# cam_cross_link.net
KiCad netlist of a schematic drawn in Altium Designer
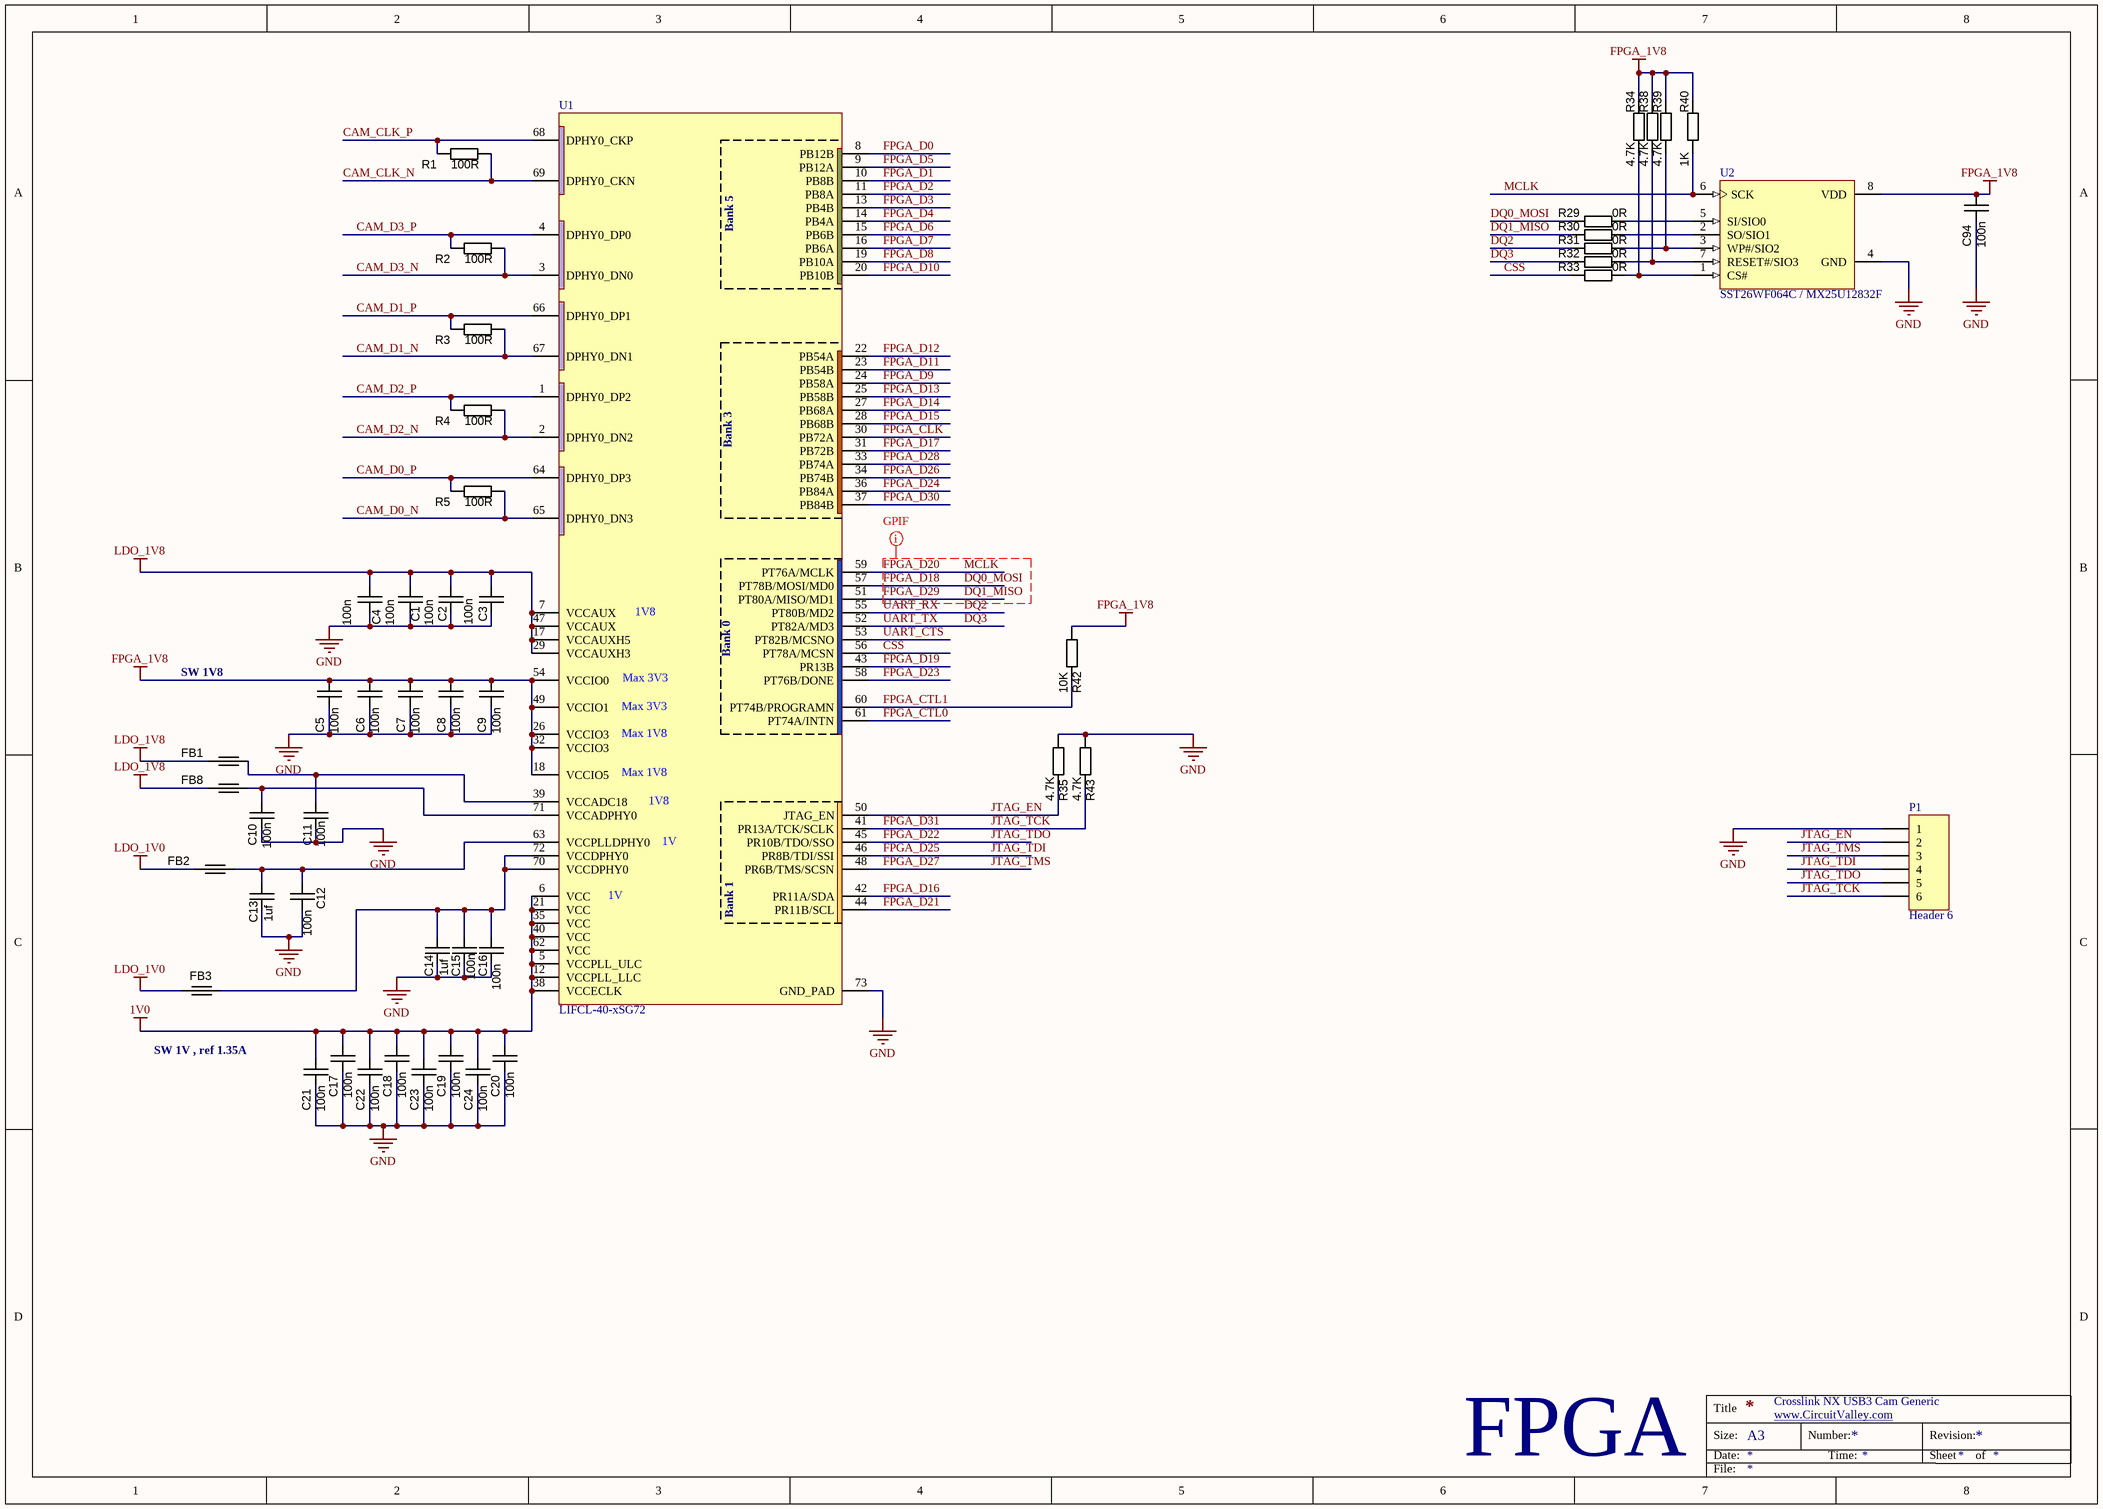
[diagram p0: cam_cross_link.SchDoc]

(export (version "E")
  (design (tool "Eeschema 10.0.6"))
  (components
    (comp (ref "C1")
      (value "100n")
      (footprint "CAPC1608N")
      (description "Capacitor SMD Cer 10pF 5% 50V NP0 0603")
      (fields (field (name "TOLERANCE") "±5%") (field (name "PART") "C0603X104K5RAC"))
      (libsource (lib "PBL - Capacitors") (part "CAPC_10p_0603_NP0_1%_50V"))
    )
    (comp (ref "C2")
      (value "100n")
      (footprint "CAPC1608N")
      (description "Capacitor SMD Cer 10pF 5% 50V NP0 0603")
      (fields (field (name "TOLERANCE") "±5%") (field (name "PART") "C0603X104K5RAC"))
      (libsource (lib "PBL - Capacitors") (part "CAPC_10p_0603_NP0_1%_50V"))
    )
    (comp (ref "C3")
      (value "100n")
      (footprint "CAPC1608N")
      (description "Capacitor SMD Cer 10pF 5% 50V NP0 0603")
      (fields (field (name "TOLERANCE") "±5%") (field (name "PART") "C0603X104K5RAC"))
      (libsource (lib "PBL - Capacitors") (part "CAPC_10p_0603_NP0_1%_50V"))
    )
    (comp (ref "C4")
      (value "100n")
      (footprint "CAPC1608N")
      (description "Capacitor SMD Cer 10pF 5% 50V NP0 0603")
      (fields (field (name "TOLERANCE") "±5%") (field (name "PART") "C0603X104K5RAC"))
      (libsource (lib "PBL - Capacitors") (part "CAPC_10p_0603_NP0_1%_50V"))
    )
    (comp (ref "C5")
      (value "100n")
      (footprint "CAPC1608N")
      (description "Capacitor SMD Cer 10pF 5% 50V NP0 0603")
      (fields (field (name "TOLERANCE") "±5%") (field (name "PART") "C0603X104K5RAC"))
      (libsource (lib "PBL - Capacitors") (part "CAPC_10p_0603_NP0_1%_50V"))
    )
    (comp (ref "C6")
      (value "100n")
      (footprint "CAPC1608N")
      (description "Capacitor SMD Cer 10pF 5% 50V NP0 0603")
      (fields (field (name "TOLERANCE") "±5%") (field (name "PART") "C0603X104K5RAC"))
      (libsource (lib "PBL - Capacitors") (part "CAPC_10p_0603_NP0_1%_50V"))
    )
    (comp (ref "C7")
      (value "100n")
      (footprint "CAPC1608N")
      (description "Capacitor SMD Cer 10pF 5% 50V NP0 0603")
      (fields (field (name "TOLERANCE") "±5%") (field (name "PART") "C0603X104K5RAC"))
      (libsource (lib "PBL - Capacitors") (part "CAPC_10p_0603_NP0_1%_50V"))
    )
    (comp (ref "C8")
      (value "100n")
      (footprint "CAPC1608N")
      (description "Capacitor SMD Cer 10pF 5% 50V NP0 0603")
      (fields (field (name "TOLERANCE") "±5%") (field (name "PART") "C0603X104K5RAC"))
      (libsource (lib "PBL - Capacitors") (part "CAPC_10p_0603_NP0_1%_50V"))
    )
    (comp (ref "C9")
      (value "100n")
      (footprint "CAPC1608N")
      (description "Capacitor SMD Cer 10pF 5% 50V NP0 0603")
      (fields (field (name "TOLERANCE") "±5%") (field (name "PART") "C0603X104K5RAC"))
      (libsource (lib "PBL - Capacitors") (part "CAPC_10p_0603_NP0_1%_50V"))
    )
    (comp (ref "C10")
      (value "100n")
      (footprint "CAPC1608N")
      (description "Capacitor SMD Cer 10pF 5% 50V NP0 0603")
      (fields (field (name "TOLERANCE") "±5%") (field (name "PART") "C0603X104K5RAC"))
      (libsource (lib "PBL - Capacitors") (part "CAPC_10p_0603_NP0_1%_50V"))
    )
    (comp (ref "C11")
      (value "100n")
      (footprint "CAPC1608N")
      (description "Capacitor SMD Cer 10pF 5% 50V NP0 0603")
      (fields (field (name "TOLERANCE") "±5%") (field (name "PART") "C0603X104K5RAC"))
      (libsource (lib "PBL - Capacitors") (part "CAPC_10p_0603_NP0_1%_50V"))
    )
    (comp (ref "C12")
      (value "100n")
      (footprint "CAPC1608N")
      (description "Capacitor SMD Cer 10pF 5% 50V NP0 0603")
      (fields (field (name "TOLERANCE") "±5%") (field (name "PART") "C0603X104K5RAC"))
      (libsource (lib "PBL - Capacitors") (part "CAPC_10p_0603_NP0_1%_50V"))
    )
    (comp (ref "C13")
      (value "1uf")
      (footprint "CAPC1608N")
      (description "Capacitor SMD Cer 10pF 5% 50V NP0 0603")
      (fields (field (name "TOLERANCE") "±5%") (field (name "PART") "C0603X104K5RAC"))
      (libsource (lib "PBL - Capacitors") (part "CAPC_10p_0603_NP0_1%_50V"))
    )
    (comp (ref "C14")
      (value "1uf")
      (footprint "CAPC1608N")
      (description "Capacitor SMD Cer 10pF 5% 50V NP0 0603")
      (fields (field (name "TOLERANCE") "±5%") (field (name "PART") "C0603X104K5RAC"))
      (libsource (lib "PBL - Capacitors") (part "CAPC_10p_0603_NP0_1%_50V"))
    )
    (comp (ref "C15")
      (value "100n")
      (footprint "CAPC1608N")
      (description "Capacitor SMD Cer 10pF 5% 50V NP0 0603")
      (fields (field (name "TOLERANCE") "±5%") (field (name "PART") "C0603X104K5RAC"))
      (libsource (lib "PBL - Capacitors") (part "CAPC_10p_0603_NP0_1%_50V"))
    )
    (comp (ref "C16")
      (value "100n")
      (footprint "CAPC1608N")
      (description "Capacitor SMD Cer 10pF 5% 50V NP0 0603")
      (fields (field (name "TOLERANCE") "±5%") (field (name "PART") "C0603X104K5RAC"))
      (libsource (lib "PBL - Capacitors") (part "CAPC_10p_0603_NP0_1%_50V"))
    )
    (comp (ref "C17")
      (value "100n")
      (footprint "CAPC1608N")
      (description "Capacitor SMD Cer 10pF 5% 50V NP0 0603")
      (fields (field (name "TOLERANCE") "±5%") (field (name "PART") "C0603X104K5RAC"))
      (libsource (lib "PBL - Capacitors") (part "CAPC_10p_0603_NP0_1%_50V"))
    )
    (comp (ref "C18")
      (value "100n")
      (footprint "CAPC1608N")
      (description "Capacitor SMD Cer 10pF 5% 50V NP0 0603")
      (fields (field (name "TOLERANCE") "±5%") (field (name "PART") "C0603X104K5RAC"))
      (libsource (lib "PBL - Capacitors") (part "CAPC_10p_0603_NP0_1%_50V"))
    )
    (comp (ref "C19")
      (value "100n")
      (footprint "CAPC1608N")
      (description "Capacitor SMD Cer 10pF 5% 50V NP0 0603")
      (fields (field (name "TOLERANCE") "±5%") (field (name "PART") "C0603X104K5RAC"))
      (libsource (lib "PBL - Capacitors") (part "CAPC_10p_0603_NP0_1%_50V"))
    )
    (comp (ref "C20")
      (value "100n")
      (footprint "CAPC1608N")
      (description "Capacitor SMD Cer 10pF 5% 50V NP0 0603")
      (fields (field (name "TOLERANCE") "±5%") (field (name "PART") "C0603X104K5RAC"))
      (libsource (lib "PBL - Capacitors") (part "CAPC_10p_0603_NP0_1%_50V"))
    )
    (comp (ref "C21")
      (value "100n")
      (footprint "CAPC1608N")
      (description "Capacitor SMD Cer 10pF 5% 50V NP0 0603")
      (fields (field (name "TOLERANCE") "±5%") (field (name "PART") "C0603X104K5RAC"))
      (libsource (lib "PBL - Capacitors") (part "CAPC_10p_0603_NP0_1%_50V"))
    )
    (comp (ref "C22")
      (value "100n")
      (footprint "CAPC1608N")
      (description "Capacitor SMD Cer 10pF 5% 50V NP0 0603")
      (fields (field (name "TOLERANCE") "±5%") (field (name "PART") "C0603X104K5RAC"))
      (libsource (lib "PBL - Capacitors") (part "CAPC_10p_0603_NP0_1%_50V"))
    )
    (comp (ref "C23")
      (value "100n")
      (footprint "CAPC1608N")
      (description "Capacitor SMD Cer 10pF 5% 50V NP0 0603")
      (fields (field (name "TOLERANCE") "±5%") (field (name "PART") "C0603X104K5RAC"))
      (libsource (lib "PBL - Capacitors") (part "CAPC_10p_0603_NP0_1%_50V"))
    )
    (comp (ref "C24")
      (value "100n")
      (footprint "CAPC1608N")
      (description "Capacitor SMD Cer 10pF 5% 50V NP0 0603")
      (fields (field (name "TOLERANCE") "±5%") (field (name "PART") "C0603X104K5RAC"))
      (libsource (lib "PBL - Capacitors") (part "CAPC_10p_0603_NP0_1%_50V"))
    )
    (comp (ref "C94")
      (value "100n")
      (footprint "CAPC1608N")
      (description "Capacitor SMD Cer 10pF 5% 50V NP0 0603")
      (fields (field (name "TOLERANCE") "±5%") (field (name "PART") "C0603X104K5RAC"))
      (libsource (lib "PBL - Capacitors") (part "CAPC_10p_0603_NP0_1%_50V"))
    )
    (comp (ref "FB1")
      (value "~")
      (footprint "FBC2012N")
      (description "Ferrite bead 2.2K Ohm at 100 MHz 200mA 0805 SMD")
      (libsource (lib "PBL - Inductors") (part "FERRITE_0805"))
    )
    (comp (ref "FB2")
      (value "~")
      (footprint "FBC2012N")
      (description "Ferrite bead 2.2K Ohm at 100 MHz 200mA 0805 SMD")
      (libsource (lib "PBL - Inductors") (part "FERRITE_0805"))
    )
    (comp (ref "FB3")
      (value "~")
      (footprint "FBC2012N")
      (description "Ferrite bead 2.2K Ohm at 100 MHz 200mA 0805 SMD")
      (libsource (lib "PBL - Inductors") (part "FERRITE_0805"))
    )
    (comp (ref "FB8")
      (value "~")
      (footprint "FBC2012N")
      (description "Ferrite bead 2.2K Ohm at 100 MHz 200mA 0805 SMD")
      (libsource (lib "PBL - Inductors") (part "FERRITE_0805"))
    )
    (comp (ref "P1")
      (value "Header 6")
      (footprint "SMD_Solder_points_1.27")
      (description "Header, 6-Pin")
      (fields (field (name "PUBLISHER") "Altium Limited"))
      (libsource (lib "Miscellaneous Connectors") (part "Header 6"))
    )
    (comp (ref "R1")
      (value "100R")
      (footprint "RESC1005N")
      (description "Resistor SMD chip 1M Ohm 0.063W 5% 0402")
      (fields (field (name "TOLERANCE") "±5%") (field (name "Comment") "Thick Film"))
      (libsource (lib "PBL - Resistors") (part "RES_1M_0402_5%"))
    )
    (comp (ref "R2")
      (value "100R")
      (footprint "RESC1005N")
      (description "Resistor SMD chip 1M Ohm 0.063W 5% 0402")
      (fields (field (name "TOLERANCE") "±5%") (field (name "Comment") "Thick Film"))
      (libsource (lib "PBL - Resistors") (part "RES_1M_0402_5%"))
    )
    (comp (ref "R3")
      (value "100R")
      (footprint "RESC1005N")
      (description "Resistor SMD chip 1M Ohm 0.063W 5% 0402")
      (fields (field (name "TOLERANCE") "±5%") (field (name "Comment") "Thick Film"))
      (libsource (lib "PBL - Resistors") (part "RES_1M_0402_5%"))
    )
    (comp (ref "R4")
      (value "100R")
      (footprint "RESC1005N")
      (description "Resistor SMD chip 1M Ohm 0.063W 5% 0402")
      (fields (field (name "TOLERANCE") "±5%") (field (name "Comment") "Thick Film"))
      (libsource (lib "PBL - Resistors") (part "RES_1M_0402_5%"))
    )
    (comp (ref "R5")
      (value "100R")
      (footprint "RESC1005N")
      (description "Resistor SMD chip 1M Ohm 0.063W 5% 0402")
      (fields (field (name "TOLERANCE") "±5%") (field (name "Comment") "Thick Film"))
      (libsource (lib "PBL - Resistors") (part "RES_1M_0402_5%"))
    )
    (comp (ref "R29")
      (value "0R")
      (footprint "RESC1608N_ZERO")
      (description "Resistor SMD chip 0.0 Ohm 0.1W 0603")
      (fields (field (name "TOLERANCE") "±5%") (field (name "Comment") "Thick Film"))
      (libsource (lib "") (part "RES_0R_0603_1"))
    )
    (comp (ref "R30")
      (value "0R")
      (footprint "RESC1608N_ZERO")
      (description "Resistor SMD chip 0.0 Ohm 0.1W 0603")
      (fields (field (name "TOLERANCE") "±5%") (field (name "Comment") "Thick Film"))
      (libsource (lib "") (part "RES_0R_0603_1"))
    )
    (comp (ref "R31")
      (value "0R")
      (footprint "RESC1608N_ZERO")
      (description "Resistor SMD chip 0.0 Ohm 0.1W 0603")
      (fields (field (name "TOLERANCE") "±5%") (field (name "Comment") "Thick Film"))
      (libsource (lib "") (part "RES_0R_0603_1"))
    )
    (comp (ref "R32")
      (value "0R")
      (footprint "RESC1608N_ZERO")
      (description "Resistor SMD chip 0.0 Ohm 0.1W 0603")
      (fields (field (name "TOLERANCE") "±5%") (field (name "Comment") "Thick Film"))
      (libsource (lib "") (part "RES_0R_0603_1"))
    )
    (comp (ref "R33")
      (value "0R")
      (footprint "RESC1608N_ZERO")
      (description "Resistor SMD chip 0.0 Ohm 0.1W 0603")
      (fields (field (name "TOLERANCE") "±5%") (field (name "Comment") "Thick Film"))
      (libsource (lib "") (part "RES_0R_0603_1"))
    )
    (comp (ref "R34")
      (value "4.7K")
      (footprint "RESC1608N_ZERO")
      (description "Resistor SMD chip 0.0 Ohm 0.1W 0603")
      (fields (field (name "TOLERANCE") "±5%") (field (name "Comment") "Thick Film"))
      (libsource (lib "PBL - Resistors") (part "RES_0R_0603"))
    )
    (comp (ref "R35")
      (value "4.7K")
      (footprint "RESC1608N_ZERO")
      (description "Resistor SMD chip 0.0 Ohm 0.1W 0603")
      (fields (field (name "TOLERANCE") "±5%") (field (name "Comment") "Thick Film"))
      (libsource (lib "PBL - Resistors") (part "RES_0R_0603"))
    )
    (comp (ref "R38")
      (value "4.7K")
      (footprint "RESC1608N_ZERO")
      (description "Resistor SMD chip 0.0 Ohm 0.1W 0603")
      (fields (field (name "TOLERANCE") "±5%") (field (name "Comment") "Thick Film"))
      (libsource (lib "PBL - Resistors") (part "RES_0R_0603"))
    )
    (comp (ref "R39")
      (value "4.7K")
      (footprint "RESC1608N_ZERO")
      (description "Resistor SMD chip 0.0 Ohm 0.1W 0603")
      (fields (field (name "TOLERANCE") "±5%") (field (name "Comment") "Thick Film"))
      (libsource (lib "PBL - Resistors") (part "RES_0R_0603"))
    )
    (comp (ref "R40")
      (value "1K")
      (footprint "RESC1608N_ZERO")
      (description "Resistor SMD chip 0.0 Ohm 0.1W 0603")
      (fields (field (name "TOLERANCE") "±5%") (field (name "Comment") "Thick Film"))
      (libsource (lib "PBL - Resistors") (part "RES_0R_0603"))
    )
    (comp (ref "R42")
      (value "10K")
      (footprint "RESC1608N_ZERO")
      (description "Resistor SMD chip 0.0 Ohm 0.1W 0603")
      (fields (field (name "TOLERANCE") "±5%") (field (name "Comment") "Thick Film"))
      (libsource (lib "PBL - Resistors") (part "RES_0R_0603"))
    )
    (comp (ref "R43")
      (value "4.7K")
      (footprint "RESC1608N_ZERO")
      (description "Resistor SMD chip 0.0 Ohm 0.1W 0603")
      (fields (field (name "TOLERANCE") "±5%") (field (name "Comment") "Thick Film"))
      (libsource (lib "PBL - Resistors") (part "RES_0R_0603"))
    )
    (comp (ref "U1")
      (value "LIFCL-40-xSG72")
      (footprint "QFN72_NX")
      (description "QFN 72 LIFCL")
      (libsource (lib "lattice_fpga") (part "LIFCL-40-xSG72"))
    )
    (comp (ref "U2")
      (value "SST26WF064C / MX25U12832F")
      (footprint "SOP8")
      (description "Flash 128Mbit for Lattice FPGA")
      (libsource (lib "cvlib") (part "MX25L12833F"))
    )
  )
  (nets
    (net (code "1") (name "/CAM_CLK_N") (class "Default")
      (node (ref "R1") (pin "1") (pinfunction "1_1") (pintype "passive"))
      (node (ref "U1") (pin "69") (pinfunction "DPHY0_CKN_69") (pintype "passive"))
    )
    (net (code "2") (name "/CAM_CLK_P") (class "Default")
      (node (ref "R1") (pin "2") (pinfunction "2_2") (pintype "passive"))
      (node (ref "U1") (pin "68") (pinfunction "DPHY0_CKP_68") (pintype "passive"))
    )
    (net (code "3") (name "/CAM_D0_N") (class "Default")
      (node (ref "R5") (pin "1") (pinfunction "1_1") (pintype "passive"))
      (node (ref "U1") (pin "65") (pinfunction "DPHY0_DN3_65") (pintype "passive"))
    )
    (net (code "4") (name "/CAM_D0_P") (class "Default")
      (node (ref "R5") (pin "2") (pinfunction "2_2") (pintype "passive"))
      (node (ref "U1") (pin "64") (pinfunction "DPHY0_DP3_64") (pintype "passive"))
    )
    (net (code "5") (name "/CAM_D1_N") (class "Default")
      (node (ref "R3") (pin "1") (pinfunction "1_1") (pintype "passive"))
      (node (ref "U1") (pin "67") (pinfunction "DPHY0_DN1_67") (pintype "passive"))
    )
    (net (code "6") (name "/CAM_D1_P") (class "Default")
      (node (ref "R3") (pin "2") (pinfunction "2_2") (pintype "passive"))
      (node (ref "U1") (pin "66") (pinfunction "DPHY0_DP1_66") (pintype "passive"))
    )
    (net (code "7") (name "/CAM_D2_N") (class "Default")
      (node (ref "R4") (pin "1") (pinfunction "1_1") (pintype "passive"))
      (node (ref "U1") (pin "2") (pinfunction "DPHY0_DN2_2") (pintype "passive"))
    )
    (net (code "8") (name "/CAM_D2_P") (class "Default")
      (node (ref "R4") (pin "2") (pinfunction "2_2") (pintype "passive"))
      (node (ref "U1") (pin "1") (pinfunction "DPHY0_DP2_1") (pintype "passive"))
    )
    (net (code "9") (name "/CAM_D3_N") (class "Default")
      (node (ref "R2") (pin "1") (pinfunction "1_1") (pintype "passive"))
      (node (ref "U1") (pin "3") (pinfunction "DPHY0_DN0_3") (pintype "passive"))
    )
    (net (code "10") (name "/CAM_D3_P") (class "Default")
      (node (ref "R2") (pin "2") (pinfunction "2_2") (pintype "passive"))
      (node (ref "U1") (pin "4") (pinfunction "DPHY0_DP0_4") (pintype "passive"))
    )
    (net (code "11") (name "/CSS") (class "Default")
      (node (ref "R33") (pin "2") (pinfunction "2_2") (pintype "passive"))
      (node (ref "U1") (pin "56") (pinfunction "PT78A/MCSN_56") (pintype "passive"))
    )
    (net (code "12") (name "/DQ0_MOSI") (class "Default")
      (node (ref "R29") (pin "2") (pinfunction "2_2") (pintype "passive"))
      (node (ref "U1") (pin "57") (pinfunction "PT78B/MOSI/MD0_57") (pintype "passive"))
    )
    (net (code "13") (name "/DQ1_MISO") (class "Default")
      (node (ref "R30") (pin "2") (pinfunction "2_2") (pintype "passive"))
      (node (ref "U1") (pin "51") (pinfunction "PT80A/MISO/MD1_51") (pintype "passive"))
    )
    (net (code "14") (name "/DQ2") (class "Default")
      (node (ref "R31") (pin "2") (pinfunction "2_2") (pintype "passive"))
      (node (ref "U1") (pin "55") (pinfunction "PT80B/MD2_55") (pintype "passive"))
    )
    (net (code "15") (name "/DQ3") (class "Default")
      (node (ref "R32") (pin "2") (pinfunction "2_2") (pintype "passive"))
      (node (ref "U1") (pin "52") (pinfunction "PT82A/MD3_52") (pintype "passive"))
    )
    (net (code "16") (name "/FPGA_CLK") (class "Default")
      (node (ref "U1") (pin "30") (pinfunction "PB72A_30") (pintype "passive"))
    )
    (net (code "17") (name "/FPGA_CTL0") (class "Default")
      (node (ref "U1") (pin "61") (pinfunction "PT74A/INTN_61") (pintype "passive"))
    )
    (net (code "18") (name "/FPGA_CTL1") (class "Default")
      (node (ref "R42") (pin "2") (pinfunction "2_2") (pintype "passive"))
      (node (ref "U1") (pin "60") (pinfunction "PT74B/PROGRAMN_60") (pintype "passive"))
    )
    (net (code "19") (name "/FPGA_D0") (class "Default")
      (node (ref "U1") (pin "8") (pinfunction "PB12B_8") (pintype "passive"))
    )
    (net (code "20") (name "/FPGA_D1") (class "Default")
      (node (ref "U1") (pin "10") (pinfunction "PB8B_10") (pintype "passive"))
    )
    (net (code "21") (name "/FPGA_D2") (class "Default")
      (node (ref "U1") (pin "11") (pinfunction "PB8A_11") (pintype "passive"))
    )
    (net (code "22") (name "/FPGA_D3") (class "Default")
      (node (ref "U1") (pin "13") (pinfunction "PB4B_13") (pintype "passive"))
    )
    (net (code "23") (name "/FPGA_D4") (class "Default")
      (node (ref "U1") (pin "14") (pinfunction "PB4A_14") (pintype "passive"))
    )
    (net (code "24") (name "/FPGA_D5") (class "Default")
      (node (ref "U1") (pin "9") (pinfunction "PB12A_9") (pintype "passive"))
    )
    (net (code "25") (name "/FPGA_D6") (class "Default")
      (node (ref "U1") (pin "15") (pinfunction "PB6B_15") (pintype "passive"))
    )
    (net (code "26") (name "/FPGA_D7") (class "Default")
      (node (ref "U1") (pin "16") (pinfunction "PB6A_16") (pintype "passive"))
    )
    (net (code "27") (name "/FPGA_D8") (class "Default")
      (node (ref "U1") (pin "19") (pinfunction "PB10A_19") (pintype "passive"))
    )
    (net (code "28") (name "/FPGA_D9") (class "Default")
      (node (ref "U1") (pin "24") (pinfunction "PB58A_24") (pintype "passive"))
    )
    (net (code "29") (name "/FPGA_D10") (class "Default")
      (node (ref "U1") (pin "20") (pinfunction "PB10B_20") (pintype "passive"))
    )
    (net (code "30") (name "/FPGA_D11") (class "Default")
      (node (ref "U1") (pin "23") (pinfunction "PB54B_23") (pintype "passive"))
    )
    (net (code "31") (name "/FPGA_D12") (class "Default")
      (node (ref "U1") (pin "22") (pinfunction "PB54A_22") (pintype "passive"))
    )
    (net (code "32") (name "/FPGA_D13") (class "Default")
      (node (ref "U1") (pin "25") (pinfunction "PB58B_25") (pintype "passive"))
    )
    (net (code "33") (name "/FPGA_D14") (class "Default")
      (node (ref "U1") (pin "27") (pinfunction "PB68A_27") (pintype "passive"))
    )
    (net (code "34") (name "/FPGA_D15") (class "Default")
      (node (ref "U1") (pin "28") (pinfunction "PB68B_28") (pintype "passive"))
    )
    (net (code "35") (name "/FPGA_D16") (class "Default")
      (node (ref "U1") (pin "42") (pinfunction "PR11A/SDA_42") (pintype "passive"))
    )
    (net (code "36") (name "/FPGA_D17") (class "Default")
      (node (ref "U1") (pin "31") (pinfunction "PB72B_31") (pintype "passive"))
    )
    (net (code "37") (name "/FPGA_D19") (class "Default")
      (node (ref "U1") (pin "43") (pinfunction "PR13B_43") (pintype "passive"))
    )
    (net (code "38") (name "/FPGA_D20") (class "Default")
      (node (ref "R40") (pin "2") (pinfunction "2_2") (pintype "passive"))
      (node (ref "U1") (pin "59") (pinfunction "PT76A/MCLK_59") (pintype "passive"))
      (node (ref "U2") (pin "6") (pinfunction "SCK_6") (pintype "input"))
    )
    (net (code "39") (name "/FPGA_D21") (class "Default")
      (node (ref "U1") (pin "44") (pinfunction "PR11B/SCL_44") (pintype "passive"))
    )
    (net (code "40") (name "/FPGA_D22") (class "Default")
      (node (ref "P1") (pin "5") (pinfunction "5_5") (pintype "passive"))
      (node (ref "U1") (pin "45") (pinfunction "PR10B/TDO/SSO_45") (pintype "passive"))
    )
    (net (code "41") (name "/FPGA_D23") (class "Default")
      (node (ref "U1") (pin "58") (pinfunction "PT76B/DONE_58") (pintype "passive"))
    )
    (net (code "42") (name "/FPGA_D24") (class "Default")
      (node (ref "U1") (pin "36") (pinfunction "PB84A_36") (pintype "passive"))
    )
    (net (code "43") (name "/FPGA_D25") (class "Default")
      (node (ref "P1") (pin "4") (pinfunction "4_4") (pintype "passive"))
      (node (ref "U1") (pin "46") (pinfunction "PR8B/TDI/SSI_46") (pintype "passive"))
    )
    (net (code "44") (name "/FPGA_D26") (class "Default")
      (node (ref "U1") (pin "34") (pinfunction "PB74B_34") (pintype "passive"))
    )
    (net (code "45") (name "/FPGA_D27") (class "Default")
      (node (ref "P1") (pin "3") (pinfunction "3_3") (pintype "passive"))
      (node (ref "U1") (pin "48") (pinfunction "PR6B/TMS/SCSN_48") (pintype "passive"))
    )
    (net (code "46") (name "/FPGA_D28") (class "Default")
      (node (ref "U1") (pin "33") (pinfunction "PB74A_33") (pintype "passive"))
    )
    (net (code "47") (name "/FPGA_D30") (class "Default")
      (node (ref "U1") (pin "37") (pinfunction "PB84B_37") (pintype "passive"))
    )
    (net (code "48") (name "/FPGA_D31") (class "Default")
      (node (ref "P1") (pin "6") (pinfunction "6_6") (pintype "passive"))
      (node (ref "R43") (pin "2") (pinfunction "2_2") (pintype "passive"))
      (node (ref "U1") (pin "41") (pinfunction "PR13A/TCK/SCLK_41") (pintype "passive"))
    )
    (net (code "49") (name "/JTAG_EN") (class "Default")
      (node (ref "P1") (pin "2") (pinfunction "2_2") (pintype "passive"))
      (node (ref "R35") (pin "2") (pinfunction "2_2") (pintype "passive"))
      (node (ref "U1") (pin "50") (pinfunction "JTAG_EN_50") (pintype "passive"))
    )
    (net (code "50") (name "/UART_CTS") (class "Default")
      (node (ref "U1") (pin "53") (pinfunction "PT82B/MCSNO_53") (pintype "passive"))
    )
    (net (code "51") (name "1V0") (class "Default")
      (node (ref "C17") (pin "2") (pintype "passive"))
      (node (ref "C18") (pin "2") (pintype "passive"))
      (node (ref "C19") (pin "2") (pintype "passive"))
      (node (ref "C20") (pin "2") (pintype "passive"))
      (node (ref "C21") (pin "2") (pintype "passive"))
      (node (ref "C22") (pin "2") (pintype "passive"))
      (node (ref "C23") (pin "2") (pintype "passive"))
      (node (ref "C24") (pin "2") (pintype "passive"))
      (node (ref "U1") (pin "12") (pinfunction "VCCPLL_LLC_12") (pintype "power_in"))
      (node (ref "U1") (pin "21") (pinfunction "VCC_21") (pintype "power_in"))
      (node (ref "U1") (pin "35") (pinfunction "VCC_35") (pintype "power_in"))
      (node (ref "U1") (pin "38") (pinfunction "VCCECLK_38") (pintype "power_in"))
      (node (ref "U1") (pin "40") (pinfunction "VCC_40") (pintype "power_in"))
      (node (ref "U1") (pin "5") (pinfunction "VCCPLL_ULC_5") (pintype "power_in"))
      (node (ref "U1") (pin "6") (pinfunction "VCC_6") (pintype "power_in"))
      (node (ref "U1") (pin "62") (pinfunction "VCC_62") (pintype "power_in"))
    )
    (net (code "52") (name "FPGA_1V8") (class "Default")
      (node (ref "C5") (pin "2") (pintype "passive"))
      (node (ref "C6") (pin "2") (pintype "passive"))
      (node (ref "C7") (pin "2") (pintype "passive"))
      (node (ref "C8") (pin "2") (pintype "passive"))
      (node (ref "C9") (pin "2") (pintype "passive"))
      (node (ref "C94") (pin "2") (pintype "passive"))
      (node (ref "R34") (pin "1") (pinfunction "1_1") (pintype "passive"))
      (node (ref "R38") (pin "1") (pinfunction "1_1") (pintype "passive"))
      (node (ref "R39") (pin "1") (pinfunction "1_1") (pintype "passive"))
      (node (ref "R40") (pin "1") (pinfunction "1_1") (pintype "passive"))
      (node (ref "R42") (pin "1") (pinfunction "1_1") (pintype "passive"))
      (node (ref "U1") (pin "18") (pinfunction "VCCIO5_18") (pintype "power_in"))
      (node (ref "U1") (pin "26") (pinfunction "VCCIO3_26") (pintype "power_in"))
      (node (ref "U1") (pin "32") (pinfunction "VCCIO3_32") (pintype "power_in"))
      (node (ref "U1") (pin "49") (pinfunction "VCCIO1_49") (pintype "power_in"))
      (node (ref "U1") (pin "54") (pinfunction "VCCIO0_54") (pintype "power_in"))
      (node (ref "U2") (pin "8") (pinfunction "VDD_8") (pintype "power_in"))
    )
    (net (code "53") (name "GND") (class "Default")
      (node (ref "C1") (pin "1") (pintype "passive"))
      (node (ref "C10") (pin "1") (pintype "passive"))
      (node (ref "C11") (pin "1") (pintype "passive"))
      (node (ref "C12") (pin "2") (pintype "passive"))
      (node (ref "C13") (pin "1") (pintype "passive"))
      (node (ref "C14") (pin "1") (pintype "passive"))
      (node (ref "C15") (pin "1") (pintype "passive"))
      (node (ref "C16") (pin "1") (pintype "passive"))
      (node (ref "C17") (pin "1") (pintype "passive"))
      (node (ref "C18") (pin "1") (pintype "passive"))
      (node (ref "C19") (pin "1") (pintype "passive"))
      (node (ref "C2") (pin "1") (pintype "passive"))
      (node (ref "C20") (pin "1") (pintype "passive"))
      (node (ref "C21") (pin "1") (pintype "passive"))
      (node (ref "C22") (pin "1") (pintype "passive"))
      (node (ref "C23") (pin "1") (pintype "passive"))
      (node (ref "C24") (pin "1") (pintype "passive"))
      (node (ref "C3") (pin "1") (pintype "passive"))
      (node (ref "C4") (pin "1") (pintype "passive"))
      (node (ref "C5") (pin "1") (pintype "passive"))
      (node (ref "C6") (pin "1") (pintype "passive"))
      (node (ref "C7") (pin "1") (pintype "passive"))
      (node (ref "C8") (pin "1") (pintype "passive"))
      (node (ref "C9") (pin "1") (pintype "passive"))
      (node (ref "C94") (pin "1") (pintype "passive"))
      (node (ref "P1") (pin "1") (pinfunction "1_1") (pintype "passive"))
      (node (ref "R35") (pin "1") (pinfunction "1_1") (pintype "passive"))
      (node (ref "R43") (pin "1") (pinfunction "1_1") (pintype "passive"))
      (node (ref "U1") (pin "73") (pinfunction "GND_PAD_73") (pintype "power_in"))
      (node (ref "U2") (pin "4") (pinfunction "GND_4") (pintype "power_in"))
    )
    (net (code "54") (name "LDO_1V0") (class "Default")
      (node (ref "FB2") (pin "1") (pinfunction "1_1") (pintype "passive"))
      (node (ref "FB3") (pin "1") (pinfunction "1_1") (pintype "passive"))
    )
    (net (code "55") (name "LDO_1V8") (class "Default")
      (node (ref "C1") (pin "2") (pintype "passive"))
      (node (ref "C2") (pin "2") (pintype "passive"))
      (node (ref "C3") (pin "2") (pintype "passive"))
      (node (ref "C4") (pin "2") (pintype "passive"))
      (node (ref "FB1") (pin "1") (pinfunction "1_1") (pintype "passive"))
      (node (ref "FB8") (pin "1") (pinfunction "1_1") (pintype "passive"))
      (node (ref "U1") (pin "17") (pinfunction "VCCAUXH5_17") (pintype "power_in"))
      (node (ref "U1") (pin "29") (pinfunction "VCCAUXH3_29") (pintype "passive"))
      (node (ref "U1") (pin "47") (pinfunction "VCCAUX_47") (pintype "power_in"))
      (node (ref "U1") (pin "7") (pinfunction "VCCAUX_7") (pintype "power_in"))
    )
    (net (code "56") (name "Net-(C14-Pad2)") (class "Default")
      (node (ref "C14") (pin "2") (pintype "passive"))
      (node (ref "C15") (pin "2") (pintype "passive"))
      (node (ref "C16") (pin "2") (pintype "passive"))
      (node (ref "FB3") (pin "2") (pinfunction "2_2") (pintype "passive"))
      (node (ref "U1") (pin "70") (pinfunction "VCCDPHY0_70") (pintype "passive"))
      (node (ref "U1") (pin "72") (pinfunction "VCCDPHY0_72") (pintype "passive"))
    )
    (net (code "57") (name "Net-(U1-VCCADC18)") (class "Default")
      (node (ref "C11") (pin "2") (pintype "passive"))
      (node (ref "FB1") (pin "2") (pinfunction "2_2") (pintype "passive"))
      (node (ref "U1") (pin "39") (pinfunction "VCCADC18_39") (pintype "power_in"))
    )
    (net (code "58") (name "Net-(U1-VCCADPHY0)") (class "Default")
      (node (ref "C10") (pin "2") (pintype "passive"))
      (node (ref "FB8") (pin "2") (pinfunction "2_2") (pintype "passive"))
      (node (ref "U1") (pin "71") (pinfunction "VCCADPHY0_71") (pintype "passive"))
    )
    (net (code "59") (name "Net-(U1-VCCPLLDPHY0)") (class "Default")
      (node (ref "C12") (pin "1") (pintype "passive"))
      (node (ref "C13") (pin "2") (pintype "passive"))
      (node (ref "FB2") (pin "2") (pinfunction "2_2") (pintype "passive"))
      (node (ref "U1") (pin "63") (pinfunction "VCCPLLDPHY0_63") (pintype "power_in"))
    )
    (net (code "60") (name "Net-(U2-CS#)") (class "Default")
      (node (ref "R33") (pin "1") (pinfunction "1_1") (pintype "passive"))
      (node (ref "R34") (pin "2") (pinfunction "2_2") (pintype "passive"))
      (node (ref "U2") (pin "1") (pinfunction "CS#_1") (pintype "input"))
    )
    (net (code "61") (name "Net-(U2-RESET#{slash}SIO3)") (class "Default")
      (node (ref "R32") (pin "1") (pinfunction "1_1") (pintype "passive"))
      (node (ref "R38") (pin "2") (pinfunction "2_2") (pintype "passive"))
      (node (ref "U2") (pin "7") (pinfunction "RESET#/SIO3_7") (pintype "input"))
    )
    (net (code "62") (name "Net-(U2-SI{slash}SIO0)") (class "Default")
      (node (ref "R29") (pin "1") (pinfunction "1_1") (pintype "passive"))
      (node (ref "U2") (pin "5") (pinfunction "SI/SIO0_5") (pintype "input"))
    )
    (net (code "63") (name "Net-(U2-SO{slash}SIO1)") (class "Default")
      (node (ref "R30") (pin "1") (pinfunction "1_1") (pintype "passive"))
      (node (ref "U2") (pin "2") (pinfunction "SO/SIO1_2") (pintype "tri_state"))
    )
    (net (code "64") (name "Net-(U2-WP#{slash}SIO2)") (class "Default")
      (node (ref "R31") (pin "1") (pinfunction "1_1") (pintype "passive"))
      (node (ref "R39") (pin "2") (pinfunction "2_2") (pintype "passive"))
      (node (ref "U2") (pin "3") (pinfunction "WP#/SIO2_3") (pintype "input"))
    )
  )
)
